# LPCB234_-_1_WIRE_DRIVER.net
KiCad netlist of a schematic drawn in Altium Designer
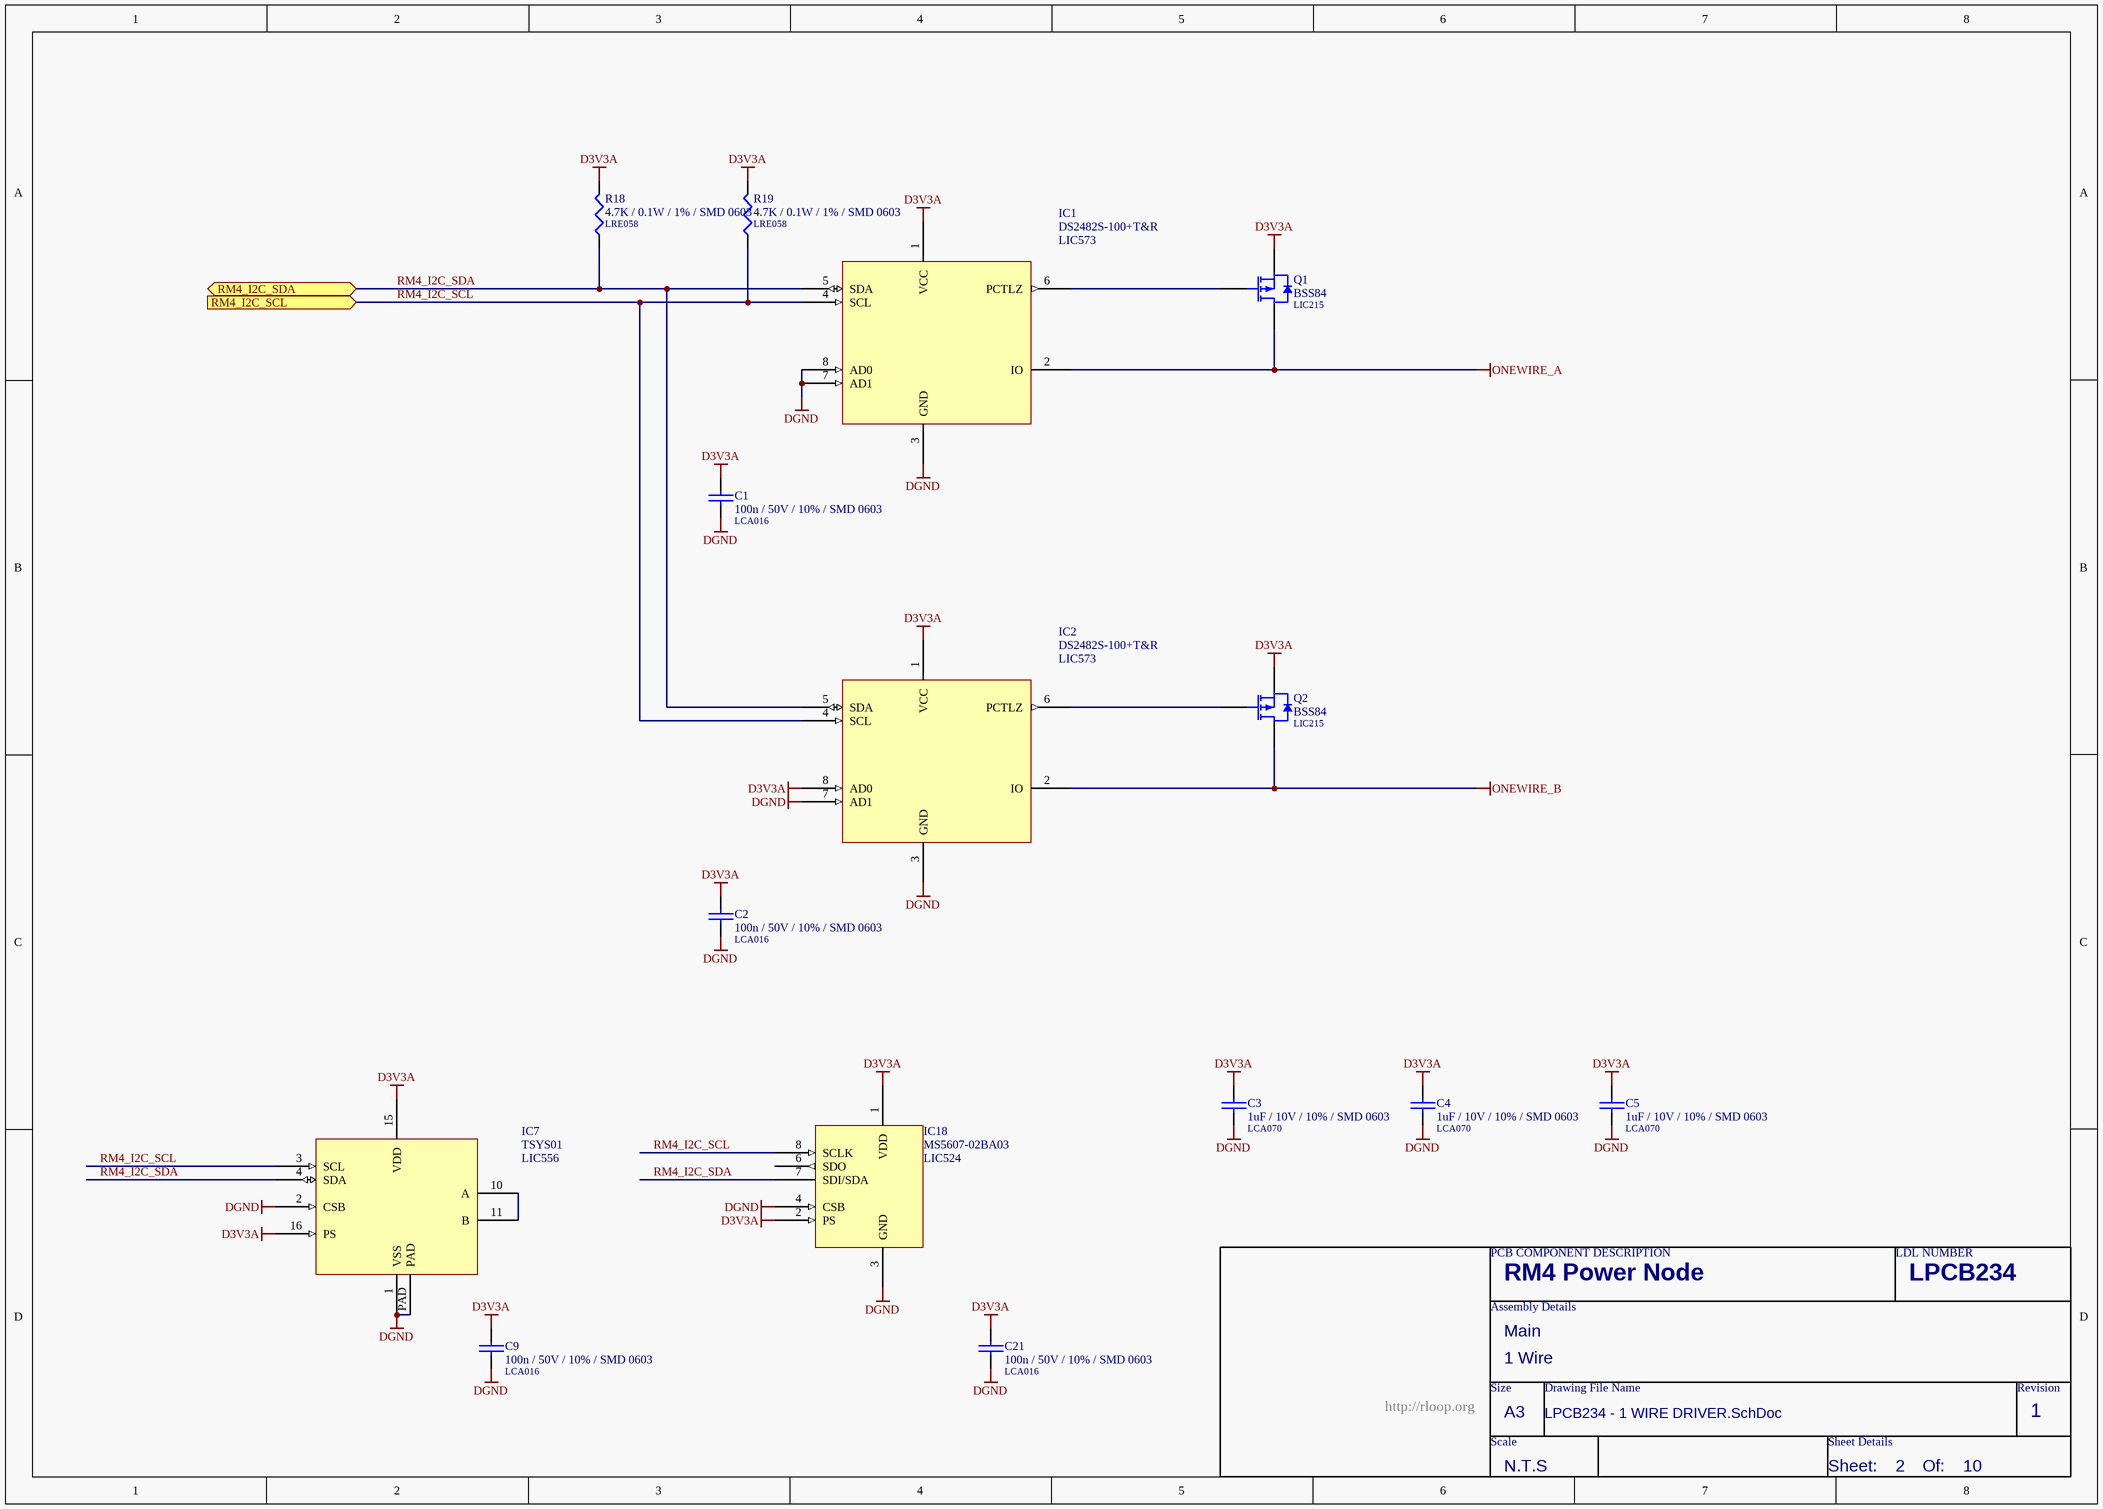
[diagram p0: LPCB234 - 1 WIRE DRIVER.SchDoc]

(export (version "E")
  (design (tool "Eeschema 10.0.6"))
  (components
    (comp (ref "C1")
      (value "100n / 50V / 10% / SMD 0603")
      (footprint "LFP011__CC1608-0603-IPC7351_B")
      (description "Capacitor, Ceramic Chip, 100nF (0.1uF), 50V, 5%, SMD 0603 [LCA016]")
      (fields (field (name "LDL_NUMBER") "LCA016"))
      (libsource (lib "LDL_Capacitors") (part "100n / 50V / 10% / SMD 0603"))
    )
    (comp (ref "C2")
      (value "100n / 50V / 10% / SMD 0603")
      (footprint "LFP011__CC1608-0603-IPC7351_B")
      (description "Capacitor, Ceramic Chip, 100nF (0.1uF), 50V, 5%, SMD 0603 [LCA016]")
      (fields (field (name "LDL_NUMBER") "LCA016"))
      (libsource (lib "LDL_Capacitors") (part "100n / 50V / 10% / SMD 0603"))
    )
    (comp (ref "C3")
      (value "1uF / 10V / 10% / SMD 0603")
      (footprint "LFP011__CC1608-0603-IPC7351_B")
      (description "Capacitor, Ceramic Chip, 1uF, 10V, SMD 0603 [LCA070]")
      (fields (field (name "LDL_NUMBER") "LCA070"))
      (libsource (lib "LDL_Capacitors") (part "1uF / 10V / 10% / SMD 0603"))
    )
    (comp (ref "C4")
      (value "1uF / 10V / 10% / SMD 0603")
      (footprint "LFP011__CC1608-0603-IPC7351_B")
      (description "Capacitor, Ceramic Chip, 1uF, 10V, SMD 0603 [LCA070]")
      (fields (field (name "LDL_NUMBER") "LCA070"))
      (libsource (lib "LDL_Capacitors") (part "1uF / 10V / 10% / SMD 0603"))
    )
    (comp (ref "C5")
      (value "1uF / 10V / 10% / SMD 0603")
      (footprint "LFP011__CC1608-0603-IPC7351_B")
      (description "Capacitor, Ceramic Chip, 1uF, 10V, SMD 0603 [LCA070]")
      (fields (field (name "LDL_NUMBER") "LCA070"))
      (libsource (lib "LDL_Capacitors") (part "1uF / 10V / 10% / SMD 0603"))
    )
    (comp (ref "C9")
      (value "100n / 50V / 10% / SMD 0603")
      (footprint "LFP011__CC1608-0603-IPC7351_B")
      (description "Capacitor, Ceramic Chip, 100nF (0.1uF), 50V, 5%, SMD 0603 [LCA016]")
      (fields (field (name "LDL_NUMBER") "LCA016"))
      (libsource (lib "LDL_Capacitors") (part "100n / 50V / 10% / SMD 0603"))
    )
    (comp (ref "C21")
      (value "100n / 50V / 10% / SMD 0603")
      (footprint "LFP011__CC1608-0603-IPC7351_B")
      (description "Capacitor, Ceramic Chip, 100nF (0.1uF), 50V, 5%, SMD 0603 [LCA016]")
      (fields (field (name "LDL_NUMBER") "LCA016"))
      (libsource (lib "LDL_Capacitors") (part "100n / 50V / 10% / SMD 0603"))
    )
    (comp (ref "IC1")
      (value "DS2482S-100+T&R")
      (footprint "LFP069__R-8G")
      (description "IC, I2C to 1 Wire Bridge, SMD SOIC8")
      (fields (field (name "LDL_NUMBER") "LIC573"))
      (libsource (lib "LDL_Semiconductors") (part "DS2482S-100+T&R"))
    )
    (comp (ref "IC2")
      (value "DS2482S-100+T&R")
      (footprint "LFP069__R-8G")
      (description "IC, I2C to 1 Wire Bridge, SMD SOIC8")
      (fields (field (name "LDL_NUMBER") "LIC573"))
      (libsource (lib "LDL_Semiconductors") (part "DS2482S-100+T&R"))
    )
    (comp (ref "IC7")
      (value "TSYS01")
      (footprint "LFP135__QFN65P400X400X80_HS-17M")
      (description "IC, Digital Temp Sensor, SMD QFN16 [LIC556]")
      (fields (field (name "LDL_NUMBER") "LIC556"))
      (libsource (lib "LDL_Semiconductors") (part "TSYS01"))
    )
    (comp (ref "IC18")
      (value "MS5607-02BA03")
      (footprint "LFP140__QFN8")
      (description "IC, Pressure Sensor IC, SMD QFN8 [LIC524]")
      (fields (field (name "LDL_NUMBER") "LIC524"))
      (libsource (lib "LDL_Semiconductors") (part "MS5607-02BA03"))
    )
    (comp (ref "Q1")
      (value "BSS84")
      (footprint "LFP021__SOT23")
      (description "FET, P Channel, Logic Level, SMD SOT23 [LIC215]")
      (fields (field (name "LDL_NUMBER") "LIC215"))
      (libsource (lib "LDL_Semiconductors") (part "BSS84"))
    )
    (comp (ref "Q2")
      (value "BSS84")
      (footprint "LFP021__SOT23")
      (description "FET, P Channel, Logic Level, SMD SOT23 [LIC215]")
      (fields (field (name "LDL_NUMBER") "LIC215"))
      (libsource (lib "LDL_Semiconductors") (part "BSS84"))
    )
    (comp (ref "R18")
      (value "4.7K / 0.1W / 1% / SMD 0603")
      (footprint "LFP020__CR1608-0603-IPC7351_B")
      (description "Resistor, Ceramic Chip, 4K7, 0.1W, 1%, SMD 0603 [LRE058]")
      (fields (field (name "LDL_NUMBER") "LRE058"))
      (libsource (lib "LDL_Resistors") (part "4.7K / 0.1W / 1% / SMD 0603"))
    )
    (comp (ref "R19")
      (value "4.7K / 0.1W / 1% / SMD 0603")
      (footprint "LFP020__CR1608-0603-IPC7351_B")
      (description "Resistor, Ceramic Chip, 4K7, 0.1W, 1%, SMD 0603 [LRE058]")
      (fields (field (name "LDL_NUMBER") "LRE058"))
      (libsource (lib "LDL_Resistors") (part "4.7K / 0.1W / 1% / SMD 0603"))
    )
  )
  (nets
    (net (code "1") (name "/RM4_I2C_SCL") (class "Default")
      (node (ref "IC1") (pin "4") (pinfunction "SCL_4") (pintype "input"))
      (node (ref "IC18") (pin "8") (pinfunction "SCLK_8") (pintype "input"))
      (node (ref "IC2") (pin "4") (pinfunction "SCL_4") (pintype "input"))
      (node (ref "IC7") (pin "3") (pinfunction "SCL_3") (pintype "input"))
      (node (ref "R19") (pin "1") (pintype "passive"))
    )
    (net (code "2") (name "/RM4_I2C_SDA") (class "Default")
      (node (ref "IC1") (pin "5") (pinfunction "SDA_5") (pintype "bidirectional"))
      (node (ref "IC18") (pin "7") (pinfunction "SDI/SDA_7") (pintype "passive"))
      (node (ref "IC2") (pin "5") (pinfunction "SDA_5") (pintype "bidirectional"))
      (node (ref "IC7") (pin "4") (pinfunction "SDA_4") (pintype "bidirectional"))
      (node (ref "R18") (pin "1") (pintype "passive"))
    )
    (net (code "3") (name "D3V3A") (class "Default")
      (node (ref "C1") (pin "1") (pintype "passive"))
      (node (ref "C2") (pin "1") (pintype "passive"))
      (node (ref "C21") (pin "1") (pintype "passive"))
      (node (ref "C3") (pin "1") (pintype "passive"))
      (node (ref "C4") (pin "1") (pintype "passive"))
      (node (ref "C5") (pin "1") (pintype "passive"))
      (node (ref "C9") (pin "1") (pintype "passive"))
      (node (ref "IC1") (pin "1") (pinfunction "VCC_1") (pintype "power_in"))
      (node (ref "IC18") (pin "1") (pinfunction "VDD_1") (pintype "power_in"))
      (node (ref "IC18") (pin "2") (pinfunction "PS_2") (pintype "input"))
      (node (ref "IC2") (pin "1") (pinfunction "VCC_1") (pintype "power_in"))
      (node (ref "IC2") (pin "8") (pinfunction "AD0_8") (pintype "input"))
      (node (ref "IC7") (pin "15") (pinfunction "VDD_15") (pintype "power_in"))
      (node (ref "IC7") (pin "16") (pinfunction "PS_16") (pintype "input"))
      (node (ref "Q1") (pin "2") (pinfunction "S_2") (pintype "passive"))
      (node (ref "Q2") (pin "2") (pinfunction "S_2") (pintype "passive"))
      (node (ref "R18") (pin "2") (pintype "passive"))
      (node (ref "R19") (pin "2") (pintype "passive"))
    )
    (net (code "4") (name "DGND") (class "Default")
      (node (ref "C1") (pin "2") (pintype "passive"))
      (node (ref "C2") (pin "2") (pintype "passive"))
      (node (ref "C21") (pin "2") (pintype "passive"))
      (node (ref "C3") (pin "2") (pintype "passive"))
      (node (ref "C4") (pin "2") (pintype "passive"))
      (node (ref "C5") (pin "2") (pintype "passive"))
      (node (ref "C9") (pin "2") (pintype "passive"))
      (node (ref "IC1") (pin "3") (pinfunction "GND_3") (pintype "power_in"))
      (node (ref "IC1") (pin "7") (pinfunction "AD1_7") (pintype "input"))
      (node (ref "IC1") (pin "8") (pinfunction "AD0_8") (pintype "input"))
      (node (ref "IC18") (pin "3") (pinfunction "GND_3") (pintype "power_in"))
      (node (ref "IC18") (pin "4") (pinfunction "CSB_4") (pintype "input"))
      (node (ref "IC2") (pin "3") (pinfunction "GND_3") (pintype "power_in"))
      (node (ref "IC2") (pin "7") (pinfunction "AD1_7") (pintype "input"))
      (node (ref "IC7") (pin "1") (pinfunction "VSS_1") (pintype "power_in"))
      (node (ref "IC7") (pin "2") (pinfunction "CSB_2") (pintype "input"))
      (node (ref "IC7") (pin "PAD") (pinfunction "PAD_PAD") (pintype "power_in"))
    )
    (net (code "5") (name "Net-(IC1-PCTLZ)") (class "Default")
      (node (ref "IC1") (pin "6") (pinfunction "PCTLZ_6") (pintype "output"))
      (node (ref "Q1") (pin "1") (pinfunction "G_1") (pintype "passive"))
    )
    (net (code "6") (name "Net-(IC2-PCTLZ)") (class "Default")
      (node (ref "IC2") (pin "6") (pinfunction "PCTLZ_6") (pintype "output"))
      (node (ref "Q2") (pin "1") (pinfunction "G_1") (pintype "passive"))
    )
    (net (code "7") (name "Net-(IC7-A)") (class "Default")
      (node (ref "IC7") (pin "10") (pinfunction "A_10") (pintype "passive"))
      (node (ref "IC7") (pin "11") (pinfunction "B_11") (pintype "passive"))
    )
    (net (code "8") (name "ONEWIRE_A") (class "Default")
      (node (ref "IC1") (pin "2") (pinfunction "IO_2") (pintype "passive"))
      (node (ref "Q1") (pin "3") (pinfunction "D_3") (pintype "passive"))
    )
    (net (code "9") (name "ONEWIRE_B") (class "Default")
      (node (ref "IC2") (pin "2") (pinfunction "IO_2") (pintype "passive"))
      (node (ref "Q2") (pin "3") (pinfunction "D_3") (pintype "passive"))
    )
    (net (code "10") (name "unconnected-(IC18-SDO-Pad6)") (class "Default")
      (node (ref "IC18") (pin "6") (pinfunction "SDO_6") (pintype "output"))
    )
  )
)
